# Board_mkIII.net
KiCad netlist of a schematic drawn in EAGLE
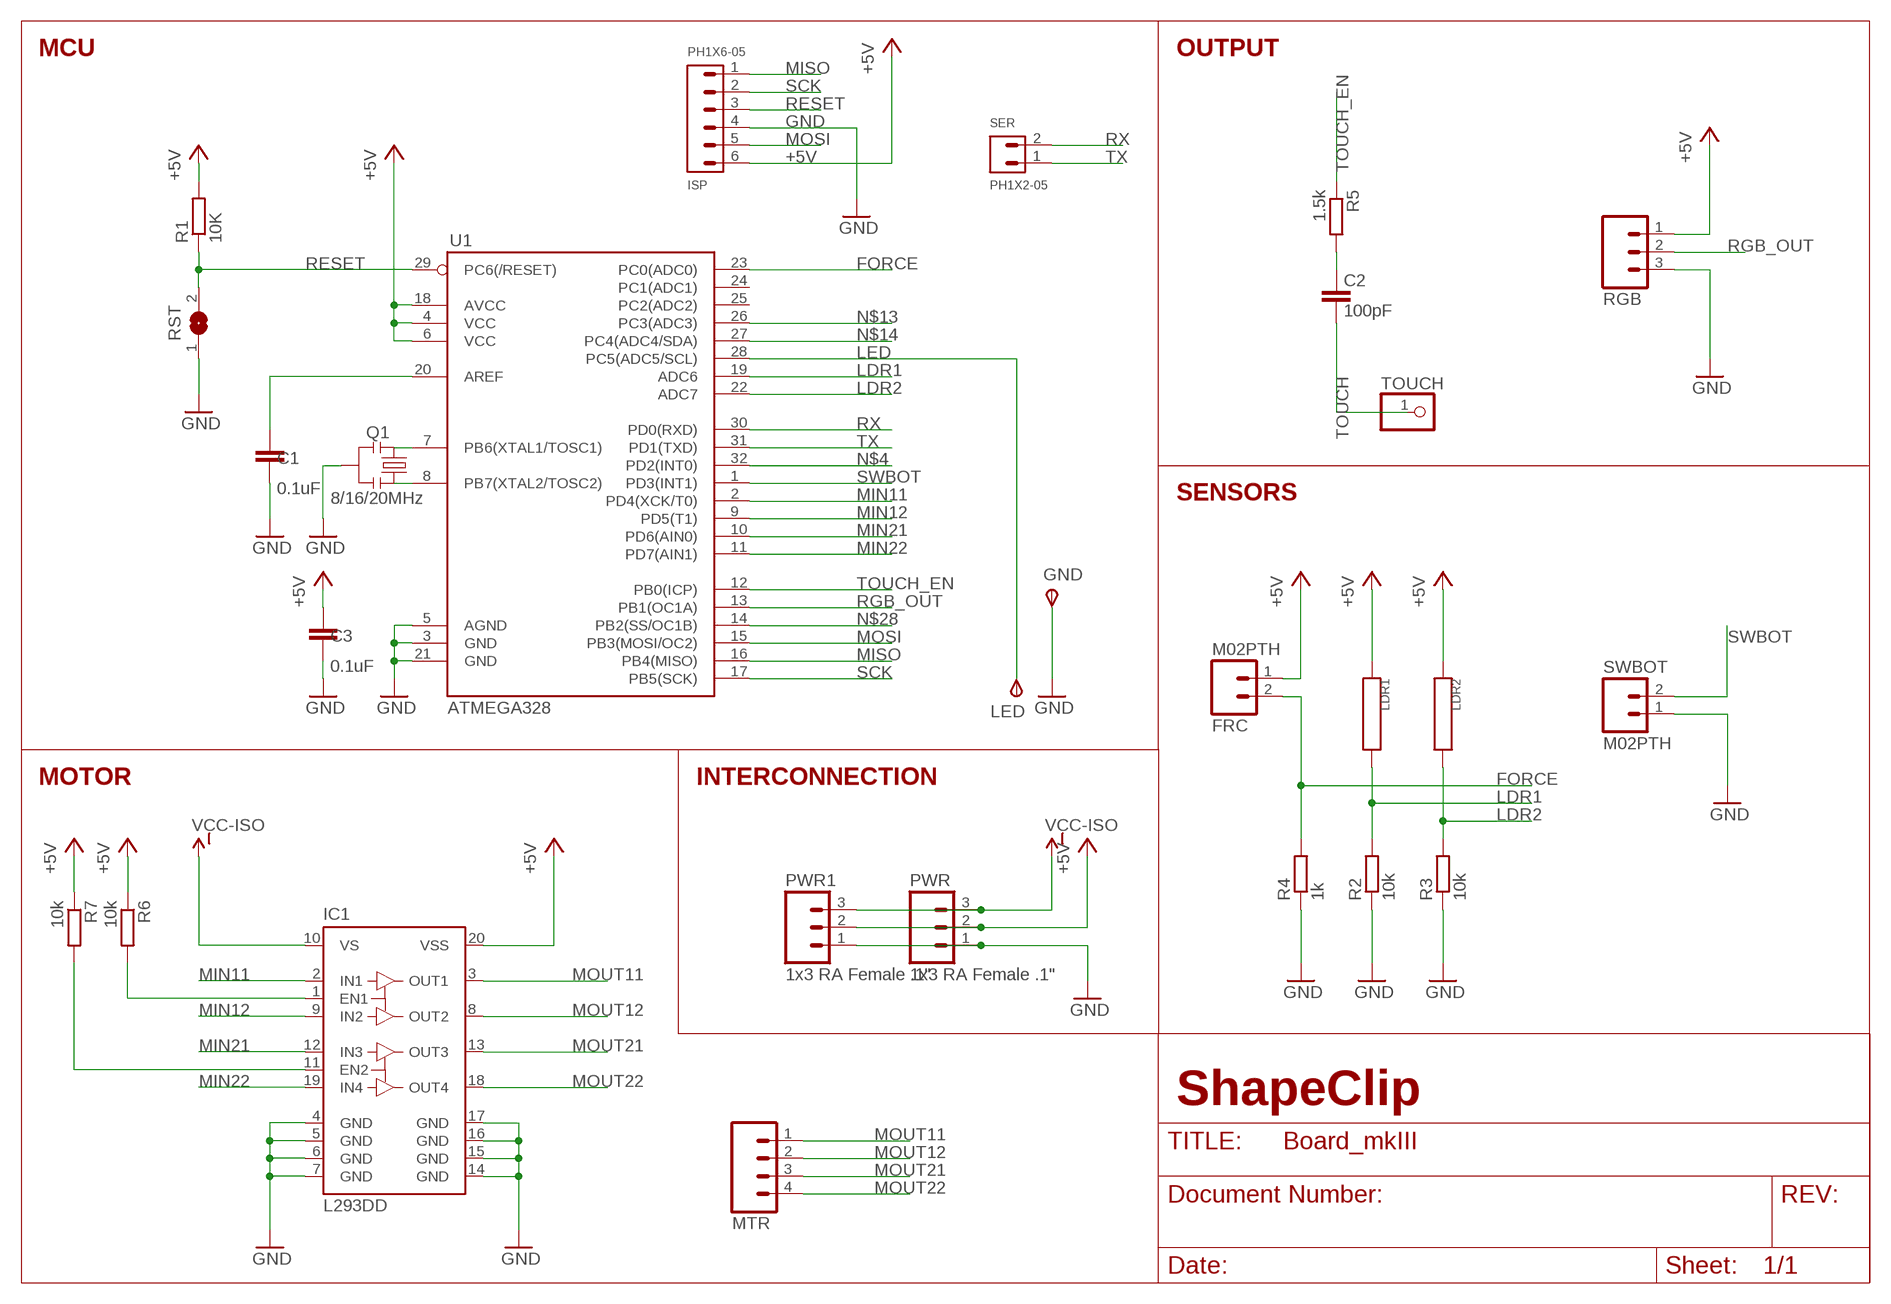
[diagram p0: schematic, sheet 1]

(export (version "E")
  (design (tool "Eeschema 10.0.6"))
  (components
    (comp (ref "C1")
      (value "0.1uF")
      (footprint "eagle-import:C0603")
      (libsource (lib "eagle-import") (part "C-EUC0603"))
    )
    (comp (ref "C2")
      (value "100pF")
      (footprint "eagle-import:C0603")
      (libsource (lib "eagle-import") (part "C-EUC0603"))
    )
    (comp (ref "C3")
      (value "0.1uF")
      (footprint "eagle-import:C0603")
      (libsource (lib "eagle-import") (part "C-EUC0603"))
    )
    (comp (ref "FRC")
      (value "M02PTH")
      (footprint "eagle-import:1X02")
      (libsource (lib "eagle-import") (part "M02PTH"))
    )
    (comp (ref "GND")
      (value "TPSTP20SQ")
      (footprint "eagle-import:TP20SQ")
      (libsource (lib "eagle-import") (part "TPSTP20SQ"))
    )
    (comp (ref "IC1")
      (value "L293DD")
      (footprint "eagle-import:SO20")
      (libsource (lib "eagle-import") (part "L293DD"))
    )
    (comp (ref "ISP")
      (value "PH1X6-05")
      (footprint "eagle-import:PH005-1-6")
      (libsource (lib "eagle-import") (part "PH1X6-05"))
    )
    (comp (ref "LDR1")
      (value "DR3-31-LDRLONG")
      (footprint "eagle-import:DR3-31-LDR_L")
      (libsource (lib "eagle-import") (part "DR3-31-LDRLONG"))
    )
    (comp (ref "LDR2")
      (value "DR3-31-LDRLONG")
      (footprint "eagle-import:DR3-31-LDR_L")
      (libsource (lib "eagle-import") (part "DR3-31-LDRLONG"))
    )
    (comp (ref "LED")
      (value "TPSTP20SQ")
      (footprint "eagle-import:TP20SQ")
      (libsource (lib "eagle-import") (part "TPSTP20SQ"))
    )
    (comp (ref "MTR")
      (value "M04PTH")
      (footprint "eagle-import:1X04")
      (libsource (lib "eagle-import") (part "M04PTH"))
    )
    (comp (ref "PWR")
      (value "1x3 RA Female .1\"")
      (footprint "eagle-import:PHD_FEMALE_3_90DEG")
      (libsource (lib "eagle-import") (part "PHD_FEMALE_3_90DEG"))
    )
    (comp (ref "PWR1")
      (value "1x3 RA Female .1\"")
      (footprint "eagle-import:PHD_FEMALE_3_90DEG")
      (libsource (lib "eagle-import") (part "PHD_FEMALE_3_90DEG"))
    )
    (comp (ref "Q1")
      (value "8/16/20MHz")
      (footprint "eagle-import:RESONATOR-SMD")
      (libsource (lib "eagle-import") (part "RESONATOR16MHZ"))
    )
    (comp (ref "R1")
      (value "10K")
      (footprint "eagle-import:R0603")
      (libsource (lib "eagle-import") (part "R-EU_R0603"))
    )
    (comp (ref "R2")
      (value "10k")
      (footprint "eagle-import:R0603")
      (libsource (lib "eagle-import") (part "R-EU_R0603"))
    )
    (comp (ref "R3")
      (value "10k")
      (footprint "eagle-import:R0603")
      (libsource (lib "eagle-import") (part "R-EU_R0603"))
    )
    (comp (ref "R4")
      (value "1k")
      (footprint "eagle-import:R0603")
      (libsource (lib "eagle-import") (part "R-EU_R0603"))
    )
    (comp (ref "R5")
      (value "1.5k")
      (footprint "eagle-import:R0603")
      (libsource (lib "eagle-import") (part "R-EU_R0603"))
    )
    (comp (ref "R6")
      (value "10k")
      (footprint "eagle-import:R0603")
      (libsource (lib "eagle-import") (part "R-EU_R0603"))
    )
    (comp (ref "R7")
      (value "10k")
      (footprint "eagle-import:R0603")
      (libsource (lib "eagle-import") (part "R-EU_R0603"))
    )
    (comp (ref "RGB")
      (value "M03PTH")
      (footprint "eagle-import:1X03")
      (libsource (lib "eagle-import") (part "M03PTH"))
    )
    (comp (ref "RST")
      (value "SJW")
      (footprint "eagle-import:SJW")
      (libsource (lib "eagle-import") (part "SJW"))
    )
    (comp (ref "SER")
      (value "PH1X2-05")
      (footprint "eagle-import:PH005-1-2")
      (libsource (lib "eagle-import") (part "PH1X2-05"))
    )
    (comp (ref "SWBOT")
      (value "M02PTH")
      (footprint "eagle-import:1X02")
      (libsource (lib "eagle-import") (part "M02PTH"))
    )
    (comp (ref "TOUCH")
      (value "PINHD-1X1")
      (footprint "eagle-import:1X01")
      (libsource (lib "eagle-import") (part "PINHD-1X1"))
    )
    (comp (ref "U1")
      (value "ATMEGA328")
      (footprint "eagle-import:TQFP32-08")
      (libsource (lib "eagle-import") (part "ATMEGA168"))
    )
  )
  (nets
    (net (code "1") (name "+5V") (class "Default")
      (node (ref "C3") (pin "2") (pinfunction "2_2") (pintype "passive"))
      (node (ref "FRC") (pin "1") (pinfunction "1_1") (pintype "passive"))
      (node (ref "IC1") (pin "20") (pinfunction "VSS_20") (pintype "power_in"))
      (node (ref "ISP") (pin "6") (pinfunction "6_6") (pintype "bidirectional"))
      (node (ref "LDR1") (pin "1") (pinfunction "P$1_1") (pintype "bidirectional"))
      (node (ref "LDR2") (pin "1") (pinfunction "P$1_1") (pintype "bidirectional"))
      (node (ref "PWR") (pin "2") (pinfunction "2_2") (pintype "passive"))
      (node (ref "PWR1") (pin "2") (pinfunction "2_2") (pintype "passive"))
      (node (ref "R1") (pin "2") (pinfunction "2_2") (pintype "passive"))
      (node (ref "R6") (pin "1") (pinfunction "1_1") (pintype "passive"))
      (node (ref "R7") (pin "1") (pinfunction "1_1") (pintype "passive"))
      (node (ref "RGB") (pin "1") (pinfunction "1_1") (pintype "passive"))
      (node (ref "U1") (pin "18") (pinfunction "AVCC_18") (pintype "bidirectional"))
      (node (ref "U1") (pin "4") (pinfunction "VCC_4") (pintype "bidirectional"))
      (node (ref "U1") (pin "6") (pinfunction "VCC_6") (pintype "bidirectional"))
    )
    (net (code "2") (name "/FORCE") (class "Default")
      (node (ref "FRC") (pin "2") (pinfunction "2_2") (pintype "passive"))
      (node (ref "R4") (pin "2") (pinfunction "2_2") (pintype "passive"))
      (node (ref "U1") (pin "23") (pinfunction "PC0(ADC0)_23") (pintype "bidirectional"))
    )
    (net (code "3") (name "/LDR1") (class "Default")
      (node (ref "LDR1") (pin "2") (pinfunction "P$2_2") (pintype "bidirectional"))
      (node (ref "R2") (pin "2") (pinfunction "2_2") (pintype "passive"))
      (node (ref "U1") (pin "19") (pinfunction "ADC6_19") (pintype "bidirectional"))
    )
    (net (code "4") (name "/LDR2") (class "Default")
      (node (ref "LDR2") (pin "2") (pinfunction "P$2_2") (pintype "bidirectional"))
      (node (ref "R3") (pin "2") (pinfunction "2_2") (pintype "passive"))
      (node (ref "U1") (pin "22") (pinfunction "ADC7_22") (pintype "bidirectional"))
    )
    (net (code "5") (name "/LED") (class "Default")
      (node (ref "LED") (pin "TP") (pinfunction "PP_TP") (pintype "input"))
      (node (ref "U1") (pin "28") (pinfunction "PC5(ADC5/SCL)_28") (pintype "bidirectional"))
    )
    (net (code "6") (name "/MIN11") (class "Default")
      (node (ref "IC1") (pin "2") (pinfunction "IN1_2") (pintype "input"))
      (node (ref "U1") (pin "2") (pinfunction "PD4(XCK/T0)_2") (pintype "bidirectional"))
    )
    (net (code "7") (name "/MIN12") (class "Default")
      (node (ref "IC1") (pin "9") (pinfunction "IN2_9") (pintype "input"))
      (node (ref "U1") (pin "9") (pinfunction "PD5(T1)_9") (pintype "bidirectional"))
    )
    (net (code "8") (name "/MIN21") (class "Default")
      (node (ref "IC1") (pin "12") (pinfunction "IN3_12") (pintype "input"))
      (node (ref "U1") (pin "10") (pinfunction "PD6(AIN0)_10") (pintype "bidirectional"))
    )
    (net (code "9") (name "/MIN22") (class "Default")
      (node (ref "IC1") (pin "19") (pinfunction "IN4_19") (pintype "input"))
      (node (ref "U1") (pin "11") (pinfunction "PD7(AIN1)_11") (pintype "bidirectional"))
    )
    (net (code "10") (name "/MISO") (class "Default")
      (node (ref "ISP") (pin "1") (pinfunction "1_1") (pintype "bidirectional"))
      (node (ref "U1") (pin "16") (pinfunction "PB4(MISO)_16") (pintype "bidirectional"))
    )
    (net (code "11") (name "/MOSI") (class "Default")
      (node (ref "ISP") (pin "5") (pinfunction "5_5") (pintype "bidirectional"))
      (node (ref "U1") (pin "15") (pinfunction "PB3(MOSI/OC2)_15") (pintype "bidirectional"))
    )
    (net (code "12") (name "/MOUT11") (class "Default")
      (node (ref "IC1") (pin "3") (pinfunction "OUT1_3") (pintype "output"))
      (node (ref "MTR") (pin "1") (pinfunction "1_1") (pintype "passive"))
    )
    (net (code "13") (name "/MOUT12") (class "Default")
      (node (ref "IC1") (pin "8") (pinfunction "OUT2_8") (pintype "output"))
      (node (ref "MTR") (pin "2") (pinfunction "2_2") (pintype "passive"))
    )
    (net (code "14") (name "/MOUT21") (class "Default")
      (node (ref "IC1") (pin "13") (pinfunction "OUT3_13") (pintype "output"))
      (node (ref "MTR") (pin "3") (pinfunction "3_3") (pintype "passive"))
    )
    (net (code "15") (name "/MOUT22") (class "Default")
      (node (ref "IC1") (pin "18") (pinfunction "OUT4_18") (pintype "output"))
      (node (ref "MTR") (pin "4") (pinfunction "4_4") (pintype "passive"))
    )
    (net (code "16") (name "/N$4") (class "Default")
      (node (ref "U1") (pin "32") (pinfunction "PD2(INT0)_32") (pintype "bidirectional"))
    )
    (net (code "17") (name "/N$13") (class "Default")
      (node (ref "U1") (pin "26") (pinfunction "PC3(ADC3)_26") (pintype "bidirectional"))
    )
    (net (code "18") (name "/N$14") (class "Default")
      (node (ref "U1") (pin "27") (pinfunction "PC4(ADC4/SDA)_27") (pintype "bidirectional"))
    )
    (net (code "19") (name "/N$28") (class "Default")
      (node (ref "U1") (pin "14") (pinfunction "PB2(SS/OC1B)_14") (pintype "bidirectional"))
    )
    (net (code "20") (name "/RESET") (class "Default")
      (node (ref "ISP") (pin "3") (pinfunction "3_3") (pintype "bidirectional"))
      (node (ref "R1") (pin "1") (pinfunction "1_1") (pintype "passive"))
      (node (ref "RST") (pin "2") (pinfunction "2_2") (pintype "passive"))
      (node (ref "U1") (pin "29") (pinfunction "PC6(/RESET)_29") (pintype "bidirectional"))
    )
    (net (code "21") (name "/RGB_OUT") (class "Default")
      (node (ref "RGB") (pin "2") (pinfunction "2_2") (pintype "passive"))
      (node (ref "U1") (pin "13") (pinfunction "PB1(OC1A)_13") (pintype "bidirectional"))
    )
    (net (code "22") (name "/RX") (class "Default")
      (node (ref "SER") (pin "2") (pinfunction "2_2") (pintype "bidirectional"))
      (node (ref "U1") (pin "30") (pinfunction "PD0(RXD)_30") (pintype "bidirectional"))
    )
    (net (code "23") (name "/SCK") (class "Default")
      (node (ref "ISP") (pin "2") (pinfunction "2_2") (pintype "bidirectional"))
      (node (ref "U1") (pin "17") (pinfunction "PB5(SCK)_17") (pintype "bidirectional"))
    )
    (net (code "24") (name "/SWBOT") (class "Default")
      (node (ref "SWBOT") (pin "2") (pinfunction "2_2") (pintype "passive"))
      (node (ref "U1") (pin "1") (pinfunction "PD3(INT1)_1") (pintype "bidirectional"))
    )
    (net (code "25") (name "/TOUCH") (class "Default")
      (node (ref "C2") (pin "1") (pinfunction "1_1") (pintype "passive"))
      (node (ref "TOUCH") (pin "1") (pinfunction "1_1") (pintype "passive"))
    )
    (net (code "26") (name "/TOUCH_EN") (class "Default")
      (node (ref "R5") (pin "1") (pinfunction "1_1") (pintype "passive"))
      (node (ref "U1") (pin "12") (pinfunction "PB0(ICP)_12") (pintype "bidirectional"))
    )
    (net (code "27") (name "/TX") (class "Default")
      (node (ref "SER") (pin "1") (pinfunction "1_1") (pintype "bidirectional"))
      (node (ref "U1") (pin "31") (pinfunction "PD1(TXD)_31") (pintype "bidirectional"))
    )
    (net (code "28") (name "GND") (class "Default")
      (node (ref "C1") (pin "1") (pinfunction "1_1") (pintype "passive"))
      (node (ref "C3") (pin "1") (pinfunction "1_1") (pintype "passive"))
      (node (ref "GND") (pin "TP") (pinfunction "PP_TP") (pintype "input"))
      (node (ref "IC1") (pin "14") (pinfunction "GND_14") (pintype "power_in"))
      (node (ref "IC1") (pin "15") (pinfunction "GND_15") (pintype "power_in"))
      (node (ref "IC1") (pin "16") (pinfunction "GND_16") (pintype "power_in"))
      (node (ref "IC1") (pin "17") (pinfunction "GND_17") (pintype "power_in"))
      (node (ref "IC1") (pin "4") (pinfunction "GND_4") (pintype "power_in"))
      (node (ref "IC1") (pin "5") (pinfunction "GND_5") (pintype "power_in"))
      (node (ref "IC1") (pin "6") (pinfunction "GND_6") (pintype "power_in"))
      (node (ref "IC1") (pin "7") (pinfunction "GND_7") (pintype "power_in"))
      (node (ref "ISP") (pin "4") (pinfunction "4_4") (pintype "bidirectional"))
      (node (ref "PWR") (pin "1") (pinfunction "1_1") (pintype "passive"))
      (node (ref "PWR1") (pin "1") (pinfunction "1_1") (pintype "passive"))
      (node (ref "Q1") (pin "2") (pinfunction "2_2") (pintype "passive"))
      (node (ref "R2") (pin "1") (pinfunction "1_1") (pintype "passive"))
      (node (ref "R3") (pin "1") (pinfunction "1_1") (pintype "passive"))
      (node (ref "R4") (pin "1") (pinfunction "1_1") (pintype "passive"))
      (node (ref "RGB") (pin "3") (pinfunction "3_3") (pintype "passive"))
      (node (ref "RST") (pin "1") (pinfunction "1_1") (pintype "passive"))
      (node (ref "SWBOT") (pin "1") (pinfunction "1_1") (pintype "passive"))
      (node (ref "U1") (pin "21") (pinfunction "GND_21") (pintype "bidirectional"))
      (node (ref "U1") (pin "3") (pinfunction "GND_3") (pintype "bidirectional"))
      (node (ref "U1") (pin "5") (pinfunction "AGND_5") (pintype "bidirectional"))
    )
    (net (code "29") (name "Net-(C2-Pad2)") (class "Default")
      (node (ref "C2") (pin "2") (pinfunction "2_2") (pintype "passive"))
      (node (ref "R5") (pin "2") (pinfunction "2_2") (pintype "passive"))
    )
    (net (code "30") (name "Net-(IC1-EN1)") (class "Default")
      (node (ref "IC1") (pin "1") (pinfunction "EN1_1") (pintype "input"))
      (node (ref "R6") (pin "2") (pinfunction "2_2") (pintype "passive"))
    )
    (net (code "31") (name "Net-(IC1-EN2)") (class "Default")
      (node (ref "IC1") (pin "11") (pinfunction "EN2_11") (pintype "input"))
      (node (ref "R7") (pin "2") (pinfunction "2_2") (pintype "passive"))
    )
    (net (code "32") (name "Net-(U1-AREF)") (class "Default")
      (node (ref "C1") (pin "2") (pinfunction "2_2") (pintype "passive"))
      (node (ref "U1") (pin "20") (pinfunction "AREF_20") (pintype "bidirectional"))
    )
    (net (code "33") (name "Net-(U1-PB6(XTAL1{slash}TOSC1))") (class "Default")
      (node (ref "Q1") (pin "3") (pinfunction "3_3") (pintype "passive"))
      (node (ref "U1") (pin "7") (pinfunction "PB6(XTAL1/TOSC1)_7") (pintype "bidirectional"))
    )
    (net (code "34") (name "Net-(U1-PB7(XTAL2{slash}TOSC2))") (class "Default")
      (node (ref "Q1") (pin "1") (pinfunction "1_1") (pintype "passive"))
      (node (ref "U1") (pin "8") (pinfunction "PB7(XTAL2/TOSC2)_8") (pintype "bidirectional"))
    )
    (net (code "35") (name "VCC-ISO") (class "Default")
      (node (ref "IC1") (pin "10") (pinfunction "VS_10") (pintype "power_in"))
      (node (ref "PWR") (pin "3") (pinfunction "3_3") (pintype "passive"))
      (node (ref "PWR1") (pin "3") (pinfunction "3_3") (pintype "passive"))
    )
    (net (code "36") (name "unconnected-(U1-PC1(ADC1)-Pad24)") (class "Default")
      (node (ref "U1") (pin "24") (pinfunction "PC1(ADC1)_24") (pintype "bidirectional"))
    )
    (net (code "37") (name "unconnected-(U1-PC2(ADC2)-Pad25)") (class "Default")
      (node (ref "U1") (pin "25") (pinfunction "PC2(ADC2)_25") (pintype "bidirectional"))
    )
  )
)
